# STORAGE.net
KiCad netlist of a schematic drawn in Altium Designer
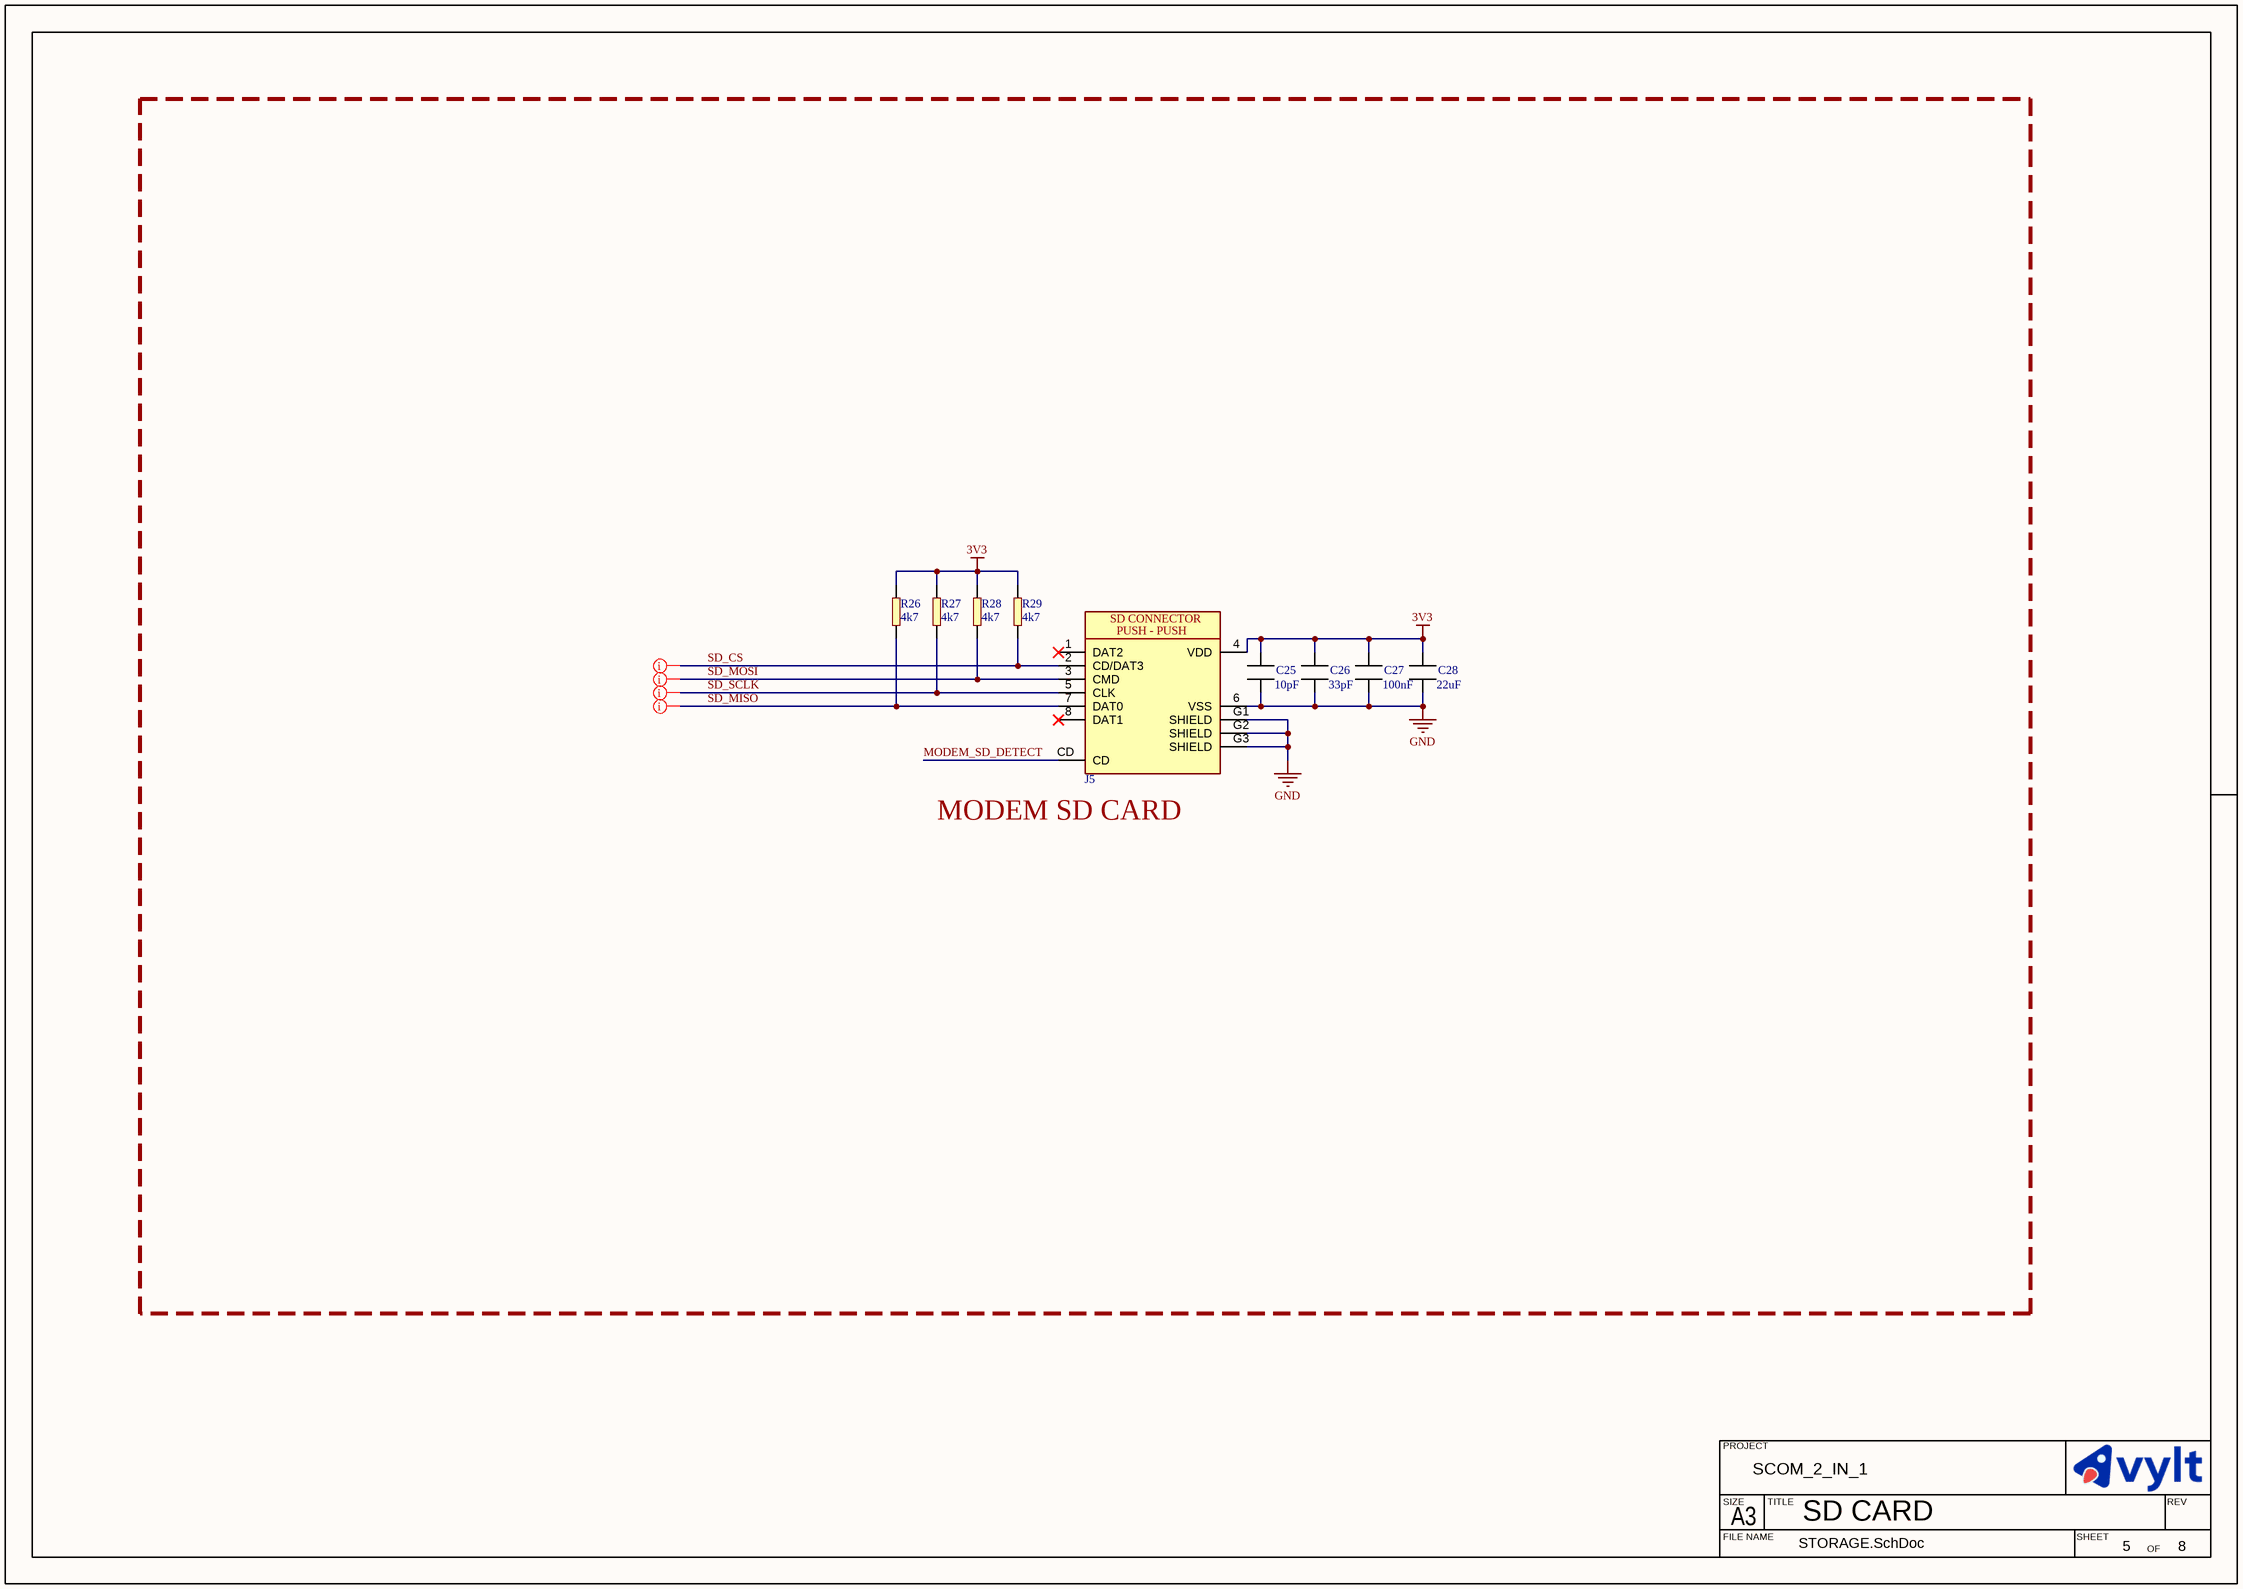
[diagram p0: STORAGE.SchDoc]

(export (version "E")
  (design (tool "Eeschema 10.0.6"))
  (components
    (comp (ref "C25")
      (value "10pF")
      (footprint "CAPC2012X13L")
      (description "Chip Capacitor, 2-Leads, Body 2.00x1.25mm, IPC High Density")
      (fields (field (name "Comment") "MLCC_0805"))
      (libsource (lib "Capacitor") (part "MLCC_0805"))
    )
    (comp (ref "C26")
      (value "33pF")
      (footprint "CAPC2012X13L")
      (description "Chip Capacitor, 2-Leads, Body 2.00x1.25mm, IPC High Density")
      (fields (field (name "Comment") "MLCC_0805"))
      (libsource (lib "Capacitor") (part "MLCC_0805"))
    )
    (comp (ref "C27")
      (value "100nF")
      (footprint "CAPC2012X13L")
      (description "Chip Capacitor, 2-Leads, Body 2.00x1.25mm, IPC High Density")
      (fields (field (name "Comment") "MLCC_0805"))
      (libsource (lib "Capacitor") (part "MLCC_0805"))
    )
    (comp (ref "C28")
      (value "22uF")
      (footprint "CAPC2012X13L")
      (description "Chip Capacitor, 2-Leads, Body 2.00x1.25mm, IPC High Density")
      (fields (field (name "Comment") "MLCC_0805"))
      (libsource (lib "Capacitor") (part "MLCC_0805"))
    )
    (comp (ref "J5")
      (value "GTFP084")
      (footprint "GTFP084")
      (description "9 (8 + 1) Position Card Connector Secure Digital - microSD™ Surface Mount, Right Angle Gold")
      (libsource (lib "Connectors") (part "GTFP084"))
    )
    (comp (ref "R26")
      (value "4k7")
      (footprint "RES_0603")
      (description "RES_0603")
      (fields (field (name "Comment") "ERP_101-1"))
      (libsource (lib "Resistor") (part "RES_0603"))
    )
    (comp (ref "R27")
      (value "4k7")
      (footprint "RES_0603")
      (description "RES_0603")
      (fields (field (name "Comment") "ERP_101-1"))
      (libsource (lib "Resistor") (part "RES_0603"))
    )
    (comp (ref "R28")
      (value "4k7")
      (footprint "RES_0603")
      (description "RES_0603")
      (fields (field (name "Comment") "ERP_101-1"))
      (libsource (lib "Resistor") (part "RES_0603"))
    )
    (comp (ref "R29")
      (value "4k7")
      (footprint "RES_0603")
      (description "RES_0603")
      (fields (field (name "Comment") "ERP_101-1"))
      (libsource (lib "Resistor") (part "RES_0603"))
    )
  )
  (nets
    (net (code "1") (name "/MODEM_SD_DETECT") (class "Default")
      (node (ref "J5") (pin "CD") (pinfunction "CD_CD") (pintype "passive"))
    )
    (net (code "2") (name "/SD_CS") (class "Default")
      (node (ref "J5") (pin "2") (pinfunction "CD/DAT3_2") (pintype "passive"))
      (node (ref "R29") (pin "1") (pinfunction "1_1") (pintype "passive"))
    )
    (net (code "3") (name "/SD_MISO") (class "Default")
      (node (ref "J5") (pin "7") (pinfunction "DAT0_7") (pintype "passive"))
      (node (ref "R26") (pin "1") (pinfunction "1_1") (pintype "passive"))
    )
    (net (code "4") (name "/SD_MOSI") (class "Default")
      (node (ref "J5") (pin "3") (pinfunction "CMD_3") (pintype "passive"))
      (node (ref "R28") (pin "1") (pinfunction "1_1") (pintype "passive"))
    )
    (net (code "5") (name "/SD_SCLK") (class "Default")
      (node (ref "J5") (pin "5") (pinfunction "CLK_5") (pintype "passive"))
      (node (ref "R27") (pin "1") (pinfunction "1_1") (pintype "passive"))
    )
    (net (code "6") (name "3V3") (class "Default")
      (node (ref "C25") (pin "1") (pinfunction "1_1") (pintype "passive"))
      (node (ref "C26") (pin "1") (pinfunction "1_1") (pintype "passive"))
      (node (ref "C27") (pin "1") (pinfunction "1_1") (pintype "passive"))
      (node (ref "C28") (pin "1") (pinfunction "1_1") (pintype "passive"))
      (node (ref "J5") (pin "4") (pinfunction "VDD_4") (pintype "passive"))
      (node (ref "R26") (pin "2") (pinfunction "2_2") (pintype "passive"))
      (node (ref "R27") (pin "2") (pinfunction "2_2") (pintype "passive"))
      (node (ref "R28") (pin "2") (pinfunction "2_2") (pintype "passive"))
      (node (ref "R29") (pin "2") (pinfunction "2_2") (pintype "passive"))
    )
    (net (code "7") (name "GND") (class "Default")
      (node (ref "C25") (pin "2") (pinfunction "2_2") (pintype "passive"))
      (node (ref "C26") (pin "2") (pinfunction "2_2") (pintype "passive"))
      (node (ref "C27") (pin "2") (pinfunction "2_2") (pintype "passive"))
      (node (ref "C28") (pin "2") (pinfunction "2_2") (pintype "passive"))
      (node (ref "J5") (pin "6") (pinfunction "VSS_6") (pintype "power_in"))
      (node (ref "J5") (pin "G1") (pinfunction "SHIELD_G1") (pintype "power_in"))
      (node (ref "J5") (pin "G2") (pinfunction "SHIELD_G2") (pintype "power_in"))
      (node (ref "J5") (pin "G3") (pinfunction "SHIELD_G3") (pintype "power_in"))
    )
    (net (code "8") (name "unconnected-(J5-DAT1-Pad8)") (class "Default")
      (node (ref "J5") (pin "8") (pinfunction "DAT1_8") (pintype "passive+no_connect"))
    )
    (net (code "9") (name "unconnected-(J5-DAT2-Pad1)") (class "Default")
      (node (ref "J5") (pin "1") (pinfunction "DAT2_1") (pintype "passive+no_connect"))
    )
  )
)
